# MusicalLights2.net
KiCad netlist of a schematic drawn in EAGLE
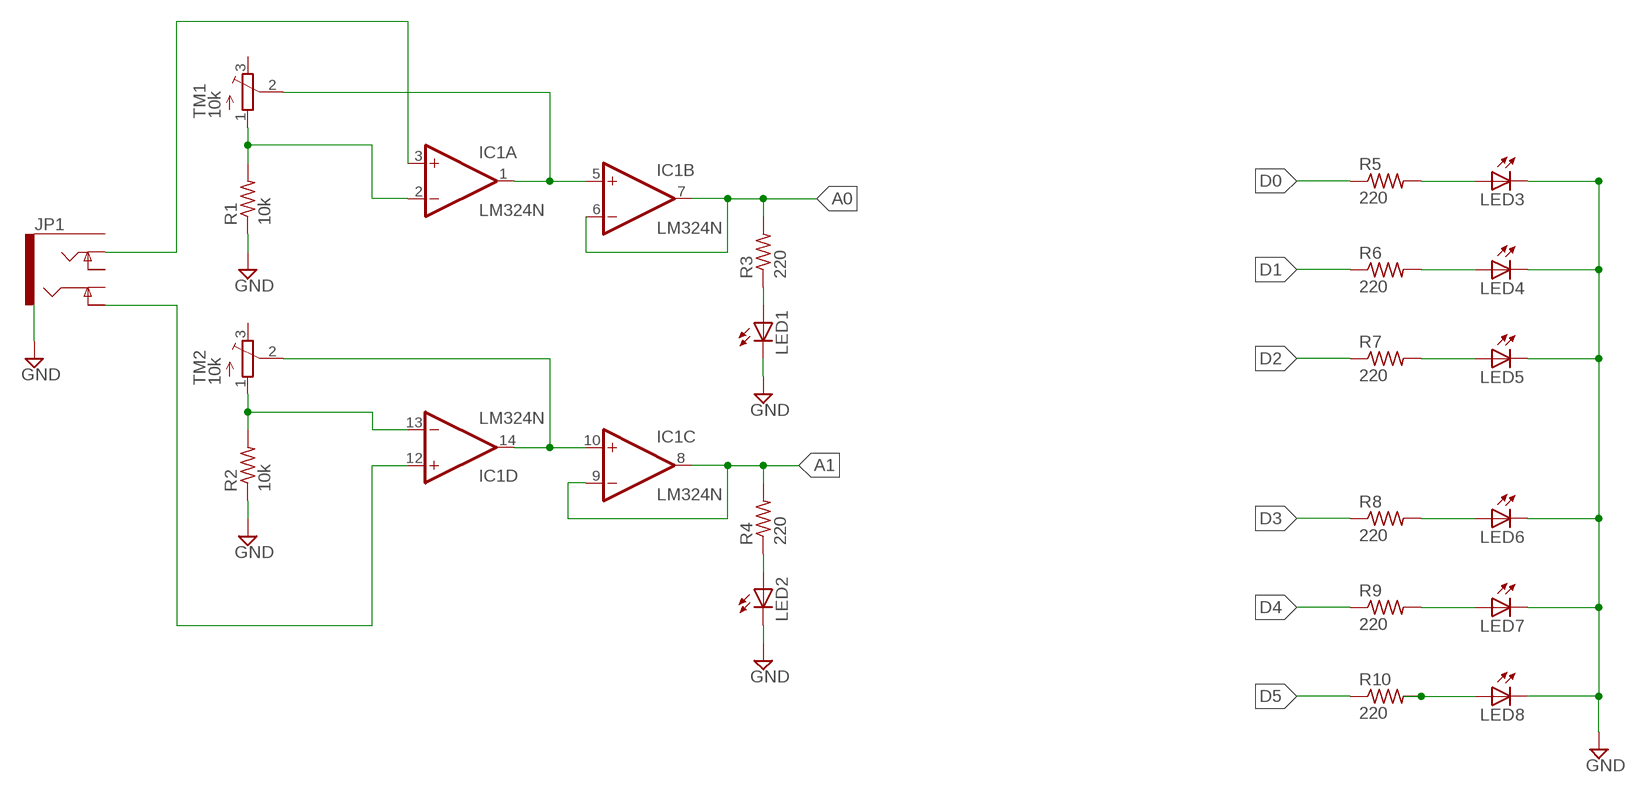
[diagram p0: schematic, sheet 1]

(export (version "E")
  (design (tool "Eeschema 10.0.6"))
  (components
    (comp (ref "IC1")
      (value "LM324N")
      (footprint "eagle-import:DIL14")
      (libsource (lib "eagle-import") (part "LM324N"))
    )
    (comp (ref "JP1")
      (value "AUDIO-JACK5-.25-VERT-TRS")
      (footprint "eagle-import:AUDIO-JACK-.25-INCH-VERT-PTH")
      (libsource (lib "eagle-import") (part "AUDIO-JACK5-.25-VERT-TRS"))
    )
    (comp (ref "LED1")
      (value "LED5MM")
      (footprint "eagle-import:LED5MM")
      (libsource (lib "eagle-import") (part "LED5MM"))
    )
    (comp (ref "LED2")
      (value "LED5MM")
      (footprint "eagle-import:LED5MM")
      (libsource (lib "eagle-import") (part "LED5MM"))
    )
    (comp (ref "LED3")
      (value "LED5MM")
      (footprint "eagle-import:LED5MM")
      (libsource (lib "eagle-import") (part "LED5MM"))
    )
    (comp (ref "LED4")
      (value "LED5MM")
      (footprint "eagle-import:LED5MM")
      (libsource (lib "eagle-import") (part "LED5MM"))
    )
    (comp (ref "LED5")
      (value "LED5MM")
      (footprint "eagle-import:LED5MM")
      (libsource (lib "eagle-import") (part "LED5MM"))
    )
    (comp (ref "LED6")
      (value "LED5MM")
      (footprint "eagle-import:LED5MM")
      (libsource (lib "eagle-import") (part "LED5MM"))
    )
    (comp (ref "LED7")
      (value "LED5MM")
      (footprint "eagle-import:LED5MM")
      (libsource (lib "eagle-import") (part "LED5MM"))
    )
    (comp (ref "LED8")
      (value "LED5MM")
      (footprint "eagle-import:LED5MM")
      (libsource (lib "eagle-import") (part "LED5MM"))
    )
    (comp (ref "R1")
      (value "10k")
      (footprint "eagle-import:0207_10")
      (libsource (lib "eagle-import") (part "R-US_0207/10"))
    )
    (comp (ref "R2")
      (value "10k")
      (footprint "eagle-import:0207_10")
      (libsource (lib "eagle-import") (part "R-US_0207/10"))
    )
    (comp (ref "R3")
      (value "220")
      (footprint "eagle-import:0207_10")
      (libsource (lib "eagle-import") (part "R-US_0207/10"))
    )
    (comp (ref "R4")
      (value "220")
      (footprint "eagle-import:0207_10")
      (libsource (lib "eagle-import") (part "R-US_0207/10"))
    )
    (comp (ref "R5")
      (value "220")
      (footprint "eagle-import:0207_10")
      (libsource (lib "eagle-import") (part "R-US_0207/10"))
    )
    (comp (ref "R6")
      (value "220")
      (footprint "eagle-import:0207_10")
      (libsource (lib "eagle-import") (part "R-US_0207/10"))
    )
    (comp (ref "R7")
      (value "220")
      (footprint "eagle-import:0207_10")
      (libsource (lib "eagle-import") (part "R-US_0207/10"))
    )
    (comp (ref "R8")
      (value "220")
      (footprint "eagle-import:0207_10")
      (libsource (lib "eagle-import") (part "R-US_0207/10"))
    )
    (comp (ref "R9")
      (value "220")
      (footprint "eagle-import:0207_10")
      (libsource (lib "eagle-import") (part "R-US_0207/10"))
    )
    (comp (ref "R10")
      (value "220")
      (footprint "eagle-import:0207_10")
      (libsource (lib "eagle-import") (part "R-US_0207/10"))
    )
    (comp (ref "TM1")
      (value "10k")
      (footprint "eagle-import:TRIM-3386")
      (libsource (lib "eagle-import") (part "TRIMPOT3386"))
    )
    (comp (ref "TM2")
      (value "10k")
      (footprint "eagle-import:TRIM-3386")
      (libsource (lib "eagle-import") (part "TRIMPOT3386"))
    )
  )
  (nets
    (net (code "1") (name "A0") (class "Default")
      (node (ref "IC1") (pin "6") (pinfunction "-IN_6") (pintype "input"))
      (node (ref "IC1") (pin "7") (pinfunction "OUT_7") (pintype "output"))
      (node (ref "R3") (pin "2") (pinfunction "2_2") (pintype "passive"))
    )
    (net (code "2") (name "A1") (class "Default")
      (node (ref "IC1") (pin "8") (pinfunction "OUT_8") (pintype "output"))
      (node (ref "IC1") (pin "9") (pinfunction "-IN_9") (pintype "input"))
      (node (ref "R4") (pin "2") (pinfunction "2_2") (pintype "passive"))
    )
    (net (code "3") (name "D0") (class "Default")
      (node (ref "R5") (pin "1") (pinfunction "1_1") (pintype "passive"))
    )
    (net (code "4") (name "D1") (class "Default")
      (node (ref "R6") (pin "1") (pinfunction "1_1") (pintype "passive"))
    )
    (net (code "5") (name "D2") (class "Default")
      (node (ref "R7") (pin "1") (pinfunction "1_1") (pintype "passive"))
    )
    (net (code "6") (name "D3") (class "Default")
      (node (ref "R8") (pin "1") (pinfunction "1_1") (pintype "passive"))
    )
    (net (code "7") (name "D4") (class "Default")
      (node (ref "R9") (pin "1") (pinfunction "1_1") (pintype "passive"))
    )
    (net (code "8") (name "D5") (class "Default")
      (node (ref "R10") (pin "1") (pinfunction "1_1") (pintype "passive"))
    )
    (net (code "9") (name "GND") (class "Default")
      (node (ref "LED1") (pin "K") (pinfunction "C_K") (pintype "passive"))
      (node (ref "LED2") (pin "K") (pinfunction "C_K") (pintype "passive"))
      (node (ref "LED3") (pin "K") (pinfunction "C_K") (pintype "passive"))
      (node (ref "LED4") (pin "K") (pinfunction "C_K") (pintype "passive"))
      (node (ref "LED5") (pin "K") (pinfunction "C_K") (pintype "passive"))
      (node (ref "LED6") (pin "K") (pinfunction "C_K") (pintype "passive"))
      (node (ref "LED7") (pin "K") (pinfunction "C_K") (pintype "passive"))
      (node (ref "LED8") (pin "K") (pinfunction "C_K") (pintype "passive"))
      (node (ref "R1") (pin "1") (pinfunction "1_1") (pintype "passive"))
      (node (ref "R2") (pin "1") (pinfunction "1_1") (pintype "passive"))
    )
    (net (code "10") (name "Net-(IC1A-+IN)") (class "Default")
      (node (ref "IC1") (pin "3") (pinfunction "+IN_3") (pintype "input"))
      (node (ref "JP1") (pin "TIP") (pinfunction "TIP_TIP") (pintype "bidirectional"))
    )
    (net (code "11") (name "Net-(IC1A--IN)") (class "Default")
      (node (ref "IC1") (pin "2") (pinfunction "-IN_2") (pintype "input"))
      (node (ref "R1") (pin "2") (pinfunction "2_2") (pintype "passive"))
      (node (ref "TM1") (pin "1") (pinfunction "A_1") (pintype "passive"))
    )
    (net (code "12") (name "Net-(IC1A-OUT)") (class "Default")
      (node (ref "IC1") (pin "1") (pinfunction "OUT_1") (pintype "output"))
      (node (ref "IC1") (pin "5") (pinfunction "+IN_5") (pintype "input"))
      (node (ref "TM1") (pin "2") (pinfunction "S_2") (pintype "passive"))
    )
    (net (code "13") (name "Net-(IC1C-+IN)") (class "Default")
      (node (ref "IC1") (pin "10") (pinfunction "+IN_10") (pintype "input"))
      (node (ref "IC1") (pin "14") (pinfunction "OUT_14") (pintype "output"))
      (node (ref "TM2") (pin "2") (pinfunction "S_2") (pintype "passive"))
    )
    (net (code "14") (name "Net-(IC1D-+IN)") (class "Default")
      (node (ref "IC1") (pin "12") (pinfunction "+IN_12") (pintype "input"))
      (node (ref "JP1") (pin "RING-NORM") (pinfunction "RING-NORM_RING-NORM") (pintype "bidirectional"))
    )
    (net (code "15") (name "Net-(IC1D--IN)") (class "Default")
      (node (ref "IC1") (pin "13") (pinfunction "-IN_13") (pintype "input"))
      (node (ref "R2") (pin "2") (pinfunction "2_2") (pintype "passive"))
      (node (ref "TM2") (pin "1") (pinfunction "A_1") (pintype "passive"))
    )
    (net (code "16") (name "Net-(LED1-PadA)") (class "Default")
      (node (ref "LED1") (pin "A") (pinfunction "A_A") (pintype "passive"))
      (node (ref "R3") (pin "1") (pinfunction "1_1") (pintype "passive"))
    )
    (net (code "17") (name "Net-(LED2-PadA)") (class "Default")
      (node (ref "LED2") (pin "A") (pinfunction "A_A") (pintype "passive"))
      (node (ref "R4") (pin "1") (pinfunction "1_1") (pintype "passive"))
    )
    (net (code "18") (name "Net-(LED3-PadA)") (class "Default")
      (node (ref "LED3") (pin "A") (pinfunction "A_A") (pintype "passive"))
      (node (ref "R5") (pin "2") (pinfunction "2_2") (pintype "passive"))
    )
    (net (code "19") (name "Net-(LED4-PadA)") (class "Default")
      (node (ref "LED4") (pin "A") (pinfunction "A_A") (pintype "passive"))
      (node (ref "R6") (pin "2") (pinfunction "2_2") (pintype "passive"))
    )
    (net (code "20") (name "Net-(LED5-PadA)") (class "Default")
      (node (ref "LED5") (pin "A") (pinfunction "A_A") (pintype "passive"))
      (node (ref "R7") (pin "2") (pinfunction "2_2") (pintype "passive"))
    )
    (net (code "21") (name "Net-(LED6-PadA)") (class "Default")
      (node (ref "LED6") (pin "A") (pinfunction "A_A") (pintype "passive"))
      (node (ref "R8") (pin "2") (pinfunction "2_2") (pintype "passive"))
    )
    (net (code "22") (name "Net-(LED7-PadA)") (class "Default")
      (node (ref "LED7") (pin "A") (pinfunction "A_A") (pintype "passive"))
      (node (ref "R9") (pin "2") (pinfunction "2_2") (pintype "passive"))
    )
    (net (code "23") (name "Net-(LED8-PadA)") (class "Default")
      (node (ref "LED8") (pin "A") (pinfunction "A_A") (pintype "passive"))
      (node (ref "R10") (pin "2") (pinfunction "2_2") (pintype "passive"))
    )
    (net (code "24") (name "unconnected-(JP1-EARTH-PadSLEEVE)") (class "Default")
      (node (ref "JP1") (pin "SLEEVE") (pinfunction "EARTH_SLEEVE") (pintype "bidirectional"))
    )
    (net (code "25") (name "unconnected-(JP1-PadRING)") (class "Default")
      (node (ref "JP1") (pin "RING") (pinfunction "RING_RING") (pintype "bidirectional"))
    )
    (net (code "26") (name "unconnected-(JP1-PadTIP-NORM)") (class "Default")
      (node (ref "JP1") (pin "TIP-NORM") (pinfunction "TIP-NORM_TIP-NORM") (pintype "bidirectional"))
    )
    (net (code "27") (name "unconnected-(TM1-E-Pad3)") (class "Default")
      (node (ref "TM1") (pin "3") (pinfunction "E_3") (pintype "passive"))
    )
    (net (code "28") (name "unconnected-(TM2-E-Pad3)") (class "Default")
      (node (ref "TM2") (pin "3") (pinfunction "E_3") (pintype "passive"))
    )
  )
)
